# ReactionWheelPCB.net
KiCad netlist of a schematic drawn in Altium Designer
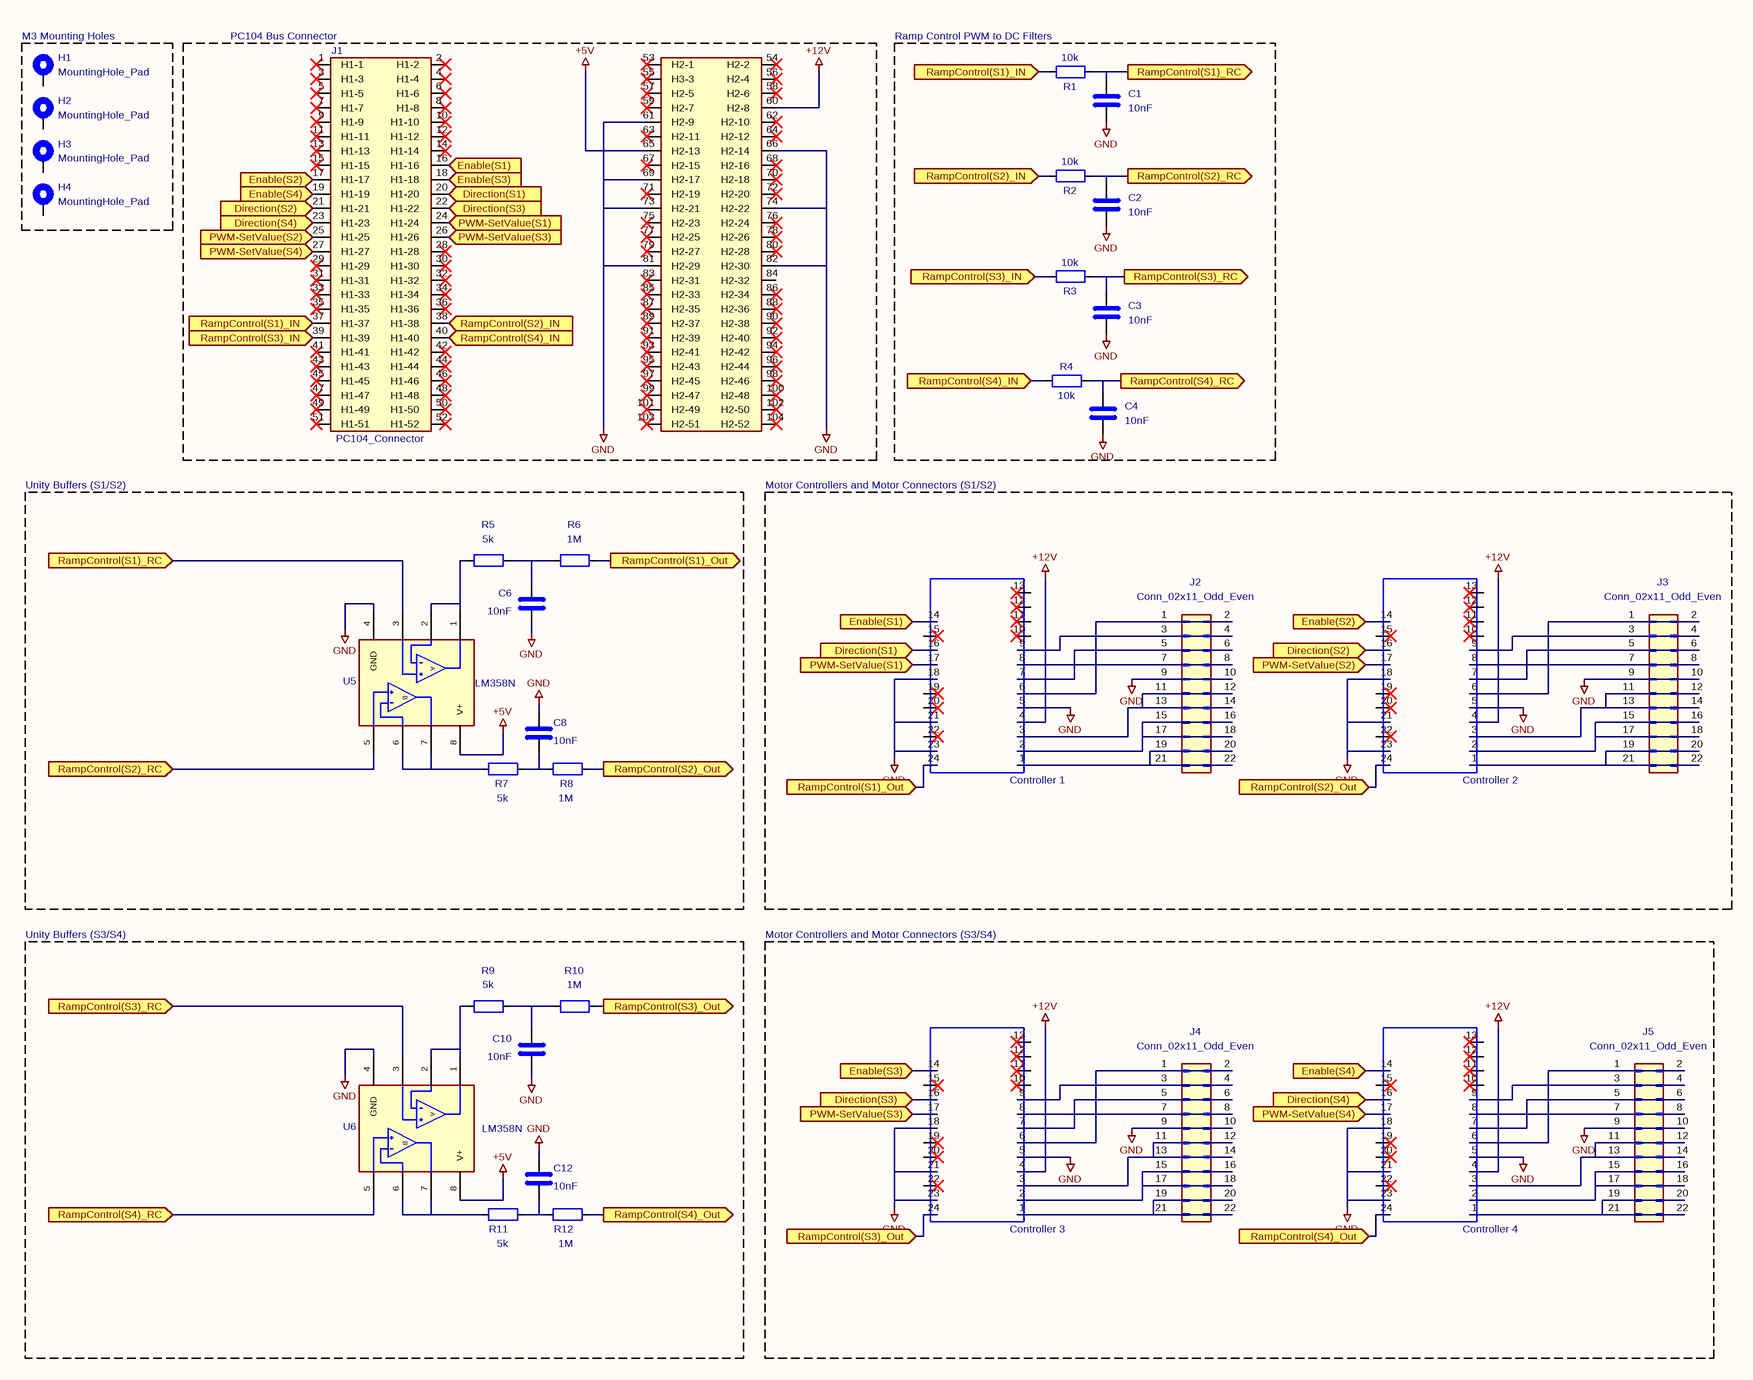
[diagram p0: ReactionWheelPCB.SchDoc]

(export (version "E")
  (design (tool "Eeschema 10.0.6"))
  (components
    (comp (ref "C1") (value "10nF") (libsource (lib "Device") (part "C")))
    (comp (ref "C2") (value "10nF") (libsource (lib "Device") (part "C")))
    (comp (ref "C3") (value "10nF") (libsource (lib "Device") (part "C")))
    (comp (ref "C4") (value "10nF") (libsource (lib "Device") (part "C")))
    (comp (ref "C6") (value "10nF") (libsource (lib "Device") (part "C")))
    (comp (ref "C8") (value "10nF") (libsource (lib "Device") (part "C")))
    (comp (ref "C10") (value "10nF") (libsource (lib "Device") (part "C")))
    (comp (ref "C12") (value "10nF") (libsource (lib "Device") (part "C")))
    (comp (ref "H1") (value "MountingHole_Pad") (libsource (lib "Mechanical") (part "MountingHole_Pad")))
    (comp (ref "H2") (value "MountingHole_Pad") (libsource (lib "Mechanical") (part "MountingHole_Pad")))
    (comp (ref "H3") (value "MountingHole_Pad") (libsource (lib "Mechanical") (part "MountingHole_Pad")))
    (comp (ref "H4") (value "MountingHole_Pad") (libsource (lib "Mechanical") (part "MountingHole_Pad")))
    (comp (ref "J1")
      (value "PC104_Connector")
      (libsource (lib "qset-connector-library") (part "PC104_Connector"))
    )
    (comp (ref "J2")
      (value "Conn_02x11_Odd_Even")
      (libsource (lib "Connector_Generic") (part "Conn_02x11_Odd_Even"))
    )
    (comp (ref "J3")
      (value "Conn_02x11_Odd_Even")
      (libsource (lib "Connector_Generic") (part "Conn_02x11_Odd_Even"))
    )
    (comp (ref "J4")
      (value "Conn_02x11_Odd_Even")
      (libsource (lib "Connector_Generic") (part "Conn_02x11_Odd_Even"))
    )
    (comp (ref "J5")
      (value "Conn_02x11_Odd_Even")
      (libsource (lib "Connector_Generic") (part "Conn_02x11_Odd_Even"))
    )
    (comp (ref "R1") (value "10k") (libsource (lib "") (part "R_1")))
    (comp (ref "R2") (value "10k") (libsource (lib "") (part "R_1")))
    (comp (ref "R3") (value "10k") (libsource (lib "") (part "R_1")))
    (comp (ref "R4") (value "10k") (libsource (lib "") (part "R_1")))
    (comp (ref "R5") (value "5k") (libsource (lib "Device") (part "R")))
    (comp (ref "R6") (value "1M") (libsource (lib "Device") (part "R")))
    (comp (ref "R7") (value "5k") (libsource (lib "") (part "R_1")))
    (comp (ref "R8") (value "1M") (libsource (lib "") (part "R_1")))
    (comp (ref "R9") (value "5k") (libsource (lib "Device") (part "R")))
    (comp (ref "R10") (value "1M") (libsource (lib "Device") (part "R")))
    (comp (ref "R11") (value "5k") (libsource (lib "") (part "R_1")))
    (comp (ref "R12") (value "1M") (libsource (lib "") (part "R_1")))
    (comp (ref "U1")
      (value "Controller 1")
      (libsource (lib "UpdatedControllerBoardSchematic-rescue") (part "Escon24.2-symbols-Controller_Board-rescue-UpdatedController-rescue"))
    )
    (comp (ref "U2")
      (value "Controller 2")
      (libsource (lib "UpdatedControllerBoardSchematic-rescue") (part "Escon24.2-symbols-Controller_Board-rescue-UpdatedController-rescue"))
    )
    (comp (ref "U3")
      (value "Controller 3")
      (libsource (lib "UpdatedControllerBoardSchematic-rescue") (part "Escon24.2-symbols-Controller_Board-rescue-UpdatedController-rescue"))
    )
    (comp (ref "U4")
      (value "Controller 4")
      (libsource (lib "UpdatedControllerBoardSchematic-rescue") (part "Escon24.2-symbols-Controller_Board-rescue-UpdatedController-rescue"))
    )
    (comp (ref "U5") (value "LM358N") (libsource (lib "ADCS_Symbols") (part "LM358")))
    (comp (ref "U6") (value "LM358N") (libsource (lib "ADCS_Symbols") (part "LM358")))
  )
  (nets
    (net (code "1") (name "+5V") (class "Default")
      (node (ref "J1") (pin "65") (pinfunction "H2-13_65") (pintype "passive"))
      (node (ref "U5") (pin "8") (pinfunction "V+_8") (pintype "passive"))
      (node (ref "U6") (pin "8") (pinfunction "V+_8") (pintype "passive"))
    )
    (net (code "2") (name "+12V") (class "Default")
      (node (ref "J1") (pin "60") (pinfunction "H2-8_60") (pintype "passive"))
      (node (ref "U1") (pin "4") (pinfunction "4_4") (pintype "passive"))
      (node (ref "U2") (pin "4") (pinfunction "4_4") (pintype "passive"))
      (node (ref "U3") (pin "4") (pinfunction "4_4") (pintype "passive"))
      (node (ref "U4") (pin "4") (pinfunction "4_4") (pintype "passive"))
    )
    (net (code "3") (name "/Direction(S1)") (class "Default")
      (node (ref "J1") (pin "20") (pinfunction "H1-20_20") (pintype "passive"))
      (node (ref "U1") (pin "16") (pinfunction "16_16") (pintype "passive"))
    )
    (net (code "4") (name "/Direction(S2)") (class "Default")
      (node (ref "J1") (pin "21") (pinfunction "H1-21_21") (pintype "passive"))
      (node (ref "U2") (pin "16") (pinfunction "16_16") (pintype "passive"))
    )
    (net (code "5") (name "/Direction(S3)") (class "Default")
      (node (ref "J1") (pin "22") (pinfunction "H1-22_22") (pintype "passive"))
      (node (ref "U3") (pin "16") (pinfunction "16_16") (pintype "passive"))
    )
    (net (code "6") (name "/Direction(S4)") (class "Default")
      (node (ref "J1") (pin "23") (pinfunction "H1-23_23") (pintype "passive"))
      (node (ref "U4") (pin "16") (pinfunction "16_16") (pintype "passive"))
    )
    (net (code "7") (name "/Enable(S1)") (class "Default")
      (node (ref "J1") (pin "16") (pinfunction "H1-16_16") (pintype "passive"))
      (node (ref "U1") (pin "14") (pinfunction "14_14") (pintype "passive"))
    )
    (net (code "8") (name "/Enable(S2)") (class "Default")
      (node (ref "J1") (pin "17") (pinfunction "H1-17_17") (pintype "passive"))
      (node (ref "U2") (pin "14") (pinfunction "14_14") (pintype "passive"))
    )
    (net (code "9") (name "/Enable(S3)") (class "Default")
      (node (ref "J1") (pin "18") (pinfunction "H1-18_18") (pintype "passive"))
      (node (ref "U3") (pin "14") (pinfunction "14_14") (pintype "passive"))
    )
    (net (code "10") (name "/Enable(S4)") (class "Default")
      (node (ref "J1") (pin "19") (pinfunction "H1-19_19") (pintype "passive"))
      (node (ref "U4") (pin "14") (pinfunction "14_14") (pintype "passive"))
    )
    (net (code "11") (name "/PWM-SetValue(S1)") (class "Default")
      (node (ref "J1") (pin "24") (pinfunction "H1-24_24") (pintype "passive"))
      (node (ref "U1") (pin "17") (pinfunction "17_17") (pintype "passive"))
    )
    (net (code "12") (name "/PWM-SetValue(S2)") (class "Default")
      (node (ref "J1") (pin "25") (pinfunction "H1-25_25") (pintype "passive"))
      (node (ref "U2") (pin "17") (pinfunction "17_17") (pintype "passive"))
    )
    (net (code "13") (name "/PWM-SetValue(S3)") (class "Default")
      (node (ref "J1") (pin "26") (pinfunction "H1-26_26") (pintype "passive"))
      (node (ref "U3") (pin "17") (pinfunction "17_17") (pintype "passive"))
    )
    (net (code "14") (name "/PWM-SetValue(S4)") (class "Default")
      (node (ref "J1") (pin "27") (pinfunction "H1-27_27") (pintype "passive"))
      (node (ref "U4") (pin "17") (pinfunction "17_17") (pintype "passive"))
    )
    (net (code "15") (name "/RampControl(S1)_IN") (class "Default")
      (node (ref "J1") (pin "37") (pinfunction "H1-37_37") (pintype "passive"))
      (node (ref "R1") (pin "1") (pinfunction "1_1") (pintype "passive"))
    )
    (net (code "16") (name "/RampControl(S1)_Out") (class "Default")
      (node (ref "R6") (pin "1") (pinfunction "1_1") (pintype "passive"))
      (node (ref "U1") (pin "24") (pinfunction "24_24") (pintype "passive"))
    )
    (net (code "17") (name "/RampControl(S1)_RC") (class "Default")
      (node (ref "C1") (pin "2") (pinfunction "2_2") (pintype "passive"))
      (node (ref "R1") (pin "2") (pinfunction "2_2") (pintype "passive"))
      (node (ref "U5") (pin "3") (pinfunction "3_3") (pintype "passive"))
    )
    (net (code "18") (name "/RampControl(S2)_IN") (class "Default")
      (node (ref "J1") (pin "38") (pinfunction "H1-38_38") (pintype "passive"))
      (node (ref "R2") (pin "1") (pinfunction "1_1") (pintype "passive"))
    )
    (net (code "19") (name "/RampControl(S2)_Out") (class "Default")
      (node (ref "R8") (pin "2") (pinfunction "2_2") (pintype "passive"))
      (node (ref "U2") (pin "24") (pinfunction "24_24") (pintype "passive"))
    )
    (net (code "20") (name "/RampControl(S2)_RC") (class "Default")
      (node (ref "C2") (pin "2") (pinfunction "2_2") (pintype "passive"))
      (node (ref "R2") (pin "2") (pinfunction "2_2") (pintype "passive"))
      (node (ref "U5") (pin "5") (pinfunction "5_5") (pintype "passive"))
    )
    (net (code "21") (name "/RampControl(S3)_IN") (class "Default")
      (node (ref "J1") (pin "39") (pinfunction "H1-39_39") (pintype "passive"))
      (node (ref "R3") (pin "1") (pinfunction "1_1") (pintype "passive"))
    )
    (net (code "22") (name "/RampControl(S3)_Out") (class "Default")
      (node (ref "R10") (pin "1") (pinfunction "1_1") (pintype "passive"))
      (node (ref "U3") (pin "24") (pinfunction "24_24") (pintype "passive"))
    )
    (net (code "23") (name "/RampControl(S3)_RC") (class "Default")
      (node (ref "C3") (pin "2") (pinfunction "2_2") (pintype "passive"))
      (node (ref "R3") (pin "2") (pinfunction "2_2") (pintype "passive"))
      (node (ref "U6") (pin "3") (pinfunction "3_3") (pintype "passive"))
    )
    (net (code "24") (name "/RampControl(S4)_IN") (class "Default")
      (node (ref "J1") (pin "40") (pinfunction "H1-40_40") (pintype "passive"))
      (node (ref "R4") (pin "1") (pinfunction "1_1") (pintype "passive"))
    )
    (net (code "25") (name "/RampControl(S4)_Out") (class "Default")
      (node (ref "R12") (pin "2") (pinfunction "2_2") (pintype "passive"))
      (node (ref "U4") (pin "24") (pinfunction "24_24") (pintype "passive"))
    )
    (net (code "26") (name "/RampControl(S4)_RC") (class "Default")
      (node (ref "C4") (pin "2") (pinfunction "2_2") (pintype "passive"))
      (node (ref "R4") (pin "2") (pinfunction "2_2") (pintype "passive"))
      (node (ref "U6") (pin "5") (pinfunction "5_5") (pintype "passive"))
    )
    (net (code "27") (name "GND") (class "Default")
      (node (ref "C1") (pin "1") (pinfunction "1_1") (pintype "passive"))
      (node (ref "C10") (pin "1") (pinfunction "1_1") (pintype "passive"))
      (node (ref "C12") (pin "1") (pinfunction "1_1") (pintype "passive"))
      (node (ref "C2") (pin "1") (pinfunction "1_1") (pintype "passive"))
      (node (ref "C3") (pin "1") (pinfunction "1_1") (pintype "passive"))
      (node (ref "C4") (pin "1") (pinfunction "1_1") (pintype "passive"))
      (node (ref "C6") (pin "1") (pinfunction "1_1") (pintype "passive"))
      (node (ref "C8") (pin "1") (pinfunction "1_1") (pintype "passive"))
      (node (ref "J1") (pin "61") (pinfunction "H2-9_61") (pintype "passive"))
      (node (ref "J1") (pin "66") (pinfunction "H2-14_66") (pintype "passive"))
      (node (ref "J1") (pin "69") (pinfunction "H2-17_69") (pintype "passive"))
      (node (ref "J1") (pin "73") (pinfunction "H2-21_73") (pintype "passive"))
      (node (ref "J1") (pin "74") (pinfunction "H2-22_74") (pintype "passive"))
      (node (ref "J1") (pin "81") (pinfunction "H2-29_81") (pintype "passive"))
      (node (ref "J1") (pin "82") (pinfunction "H2-30_82") (pintype "passive"))
      (node (ref "J2") (pin "10") (pinfunction "Pin_10_10") (pintype "passive"))
      (node (ref "J2") (pin "9") (pinfunction "Pin_9_9") (pintype "passive"))
      (node (ref "J3") (pin "10") (pinfunction "Pin_10_10") (pintype "passive"))
      (node (ref "J3") (pin "9") (pinfunction "Pin_9_9") (pintype "passive"))
      (node (ref "J4") (pin "10") (pinfunction "Pin_10_10") (pintype "passive"))
      (node (ref "J4") (pin "9") (pinfunction "Pin_9_9") (pintype "passive"))
      (node (ref "J5") (pin "10") (pinfunction "Pin_10_10") (pintype "passive"))
      (node (ref "J5") (pin "9") (pinfunction "Pin_9_9") (pintype "passive"))
      (node (ref "U1") (pin "18") (pinfunction "18_18") (pintype "passive"))
      (node (ref "U1") (pin "21") (pinfunction "21_21") (pintype "passive"))
      (node (ref "U1") (pin "23") (pinfunction "23_23") (pintype "passive"))
      (node (ref "U1") (pin "5") (pinfunction "5_5") (pintype "passive"))
      (node (ref "U2") (pin "18") (pinfunction "18_18") (pintype "passive"))
      (node (ref "U2") (pin "21") (pinfunction "21_21") (pintype "passive"))
      (node (ref "U2") (pin "23") (pinfunction "23_23") (pintype "passive"))
      (node (ref "U2") (pin "5") (pinfunction "5_5") (pintype "passive"))
      (node (ref "U3") (pin "18") (pinfunction "18_18") (pintype "passive"))
      (node (ref "U3") (pin "21") (pinfunction "21_21") (pintype "passive"))
      (node (ref "U3") (pin "23") (pinfunction "23_23") (pintype "passive"))
      (node (ref "U3") (pin "5") (pinfunction "5_5") (pintype "passive"))
      (node (ref "U4") (pin "18") (pinfunction "18_18") (pintype "passive"))
      (node (ref "U4") (pin "21") (pinfunction "21_21") (pintype "passive"))
      (node (ref "U4") (pin "23") (pinfunction "23_23") (pintype "passive"))
      (node (ref "U4") (pin "5") (pinfunction "5_5") (pintype "passive"))
      (node (ref "U5") (pin "4") (pinfunction "GND_4") (pintype "passive"))
      (node (ref "U6") (pin "4") (pinfunction "GND_4") (pintype "passive"))
    )
    (net (code "28") (name "Net-(C6-Pad2)") (class "Default")
      (node (ref "C6") (pin "2") (pinfunction "2_2") (pintype "passive"))
      (node (ref "R5") (pin "1") (pinfunction "1_1") (pintype "passive"))
      (node (ref "R6") (pin "2") (pinfunction "2_2") (pintype "passive"))
    )
    (net (code "29") (name "Net-(C8-Pad2)") (class "Default")
      (node (ref "C8") (pin "2") (pinfunction "2_2") (pintype "passive"))
      (node (ref "R7") (pin "2") (pinfunction "2_2") (pintype "passive"))
      (node (ref "R8") (pin "1") (pinfunction "1_1") (pintype "passive"))
    )
    (net (code "30") (name "Net-(C10-Pad2)") (class "Default")
      (node (ref "C10") (pin "2") (pinfunction "2_2") (pintype "passive"))
      (node (ref "R10") (pin "2") (pinfunction "2_2") (pintype "passive"))
      (node (ref "R9") (pin "1") (pinfunction "1_1") (pintype "passive"))
    )
    (net (code "31") (name "Net-(C12-Pad2)") (class "Default")
      (node (ref "C12") (pin "2") (pinfunction "2_2") (pintype "passive"))
      (node (ref "R11") (pin "2") (pinfunction "2_2") (pintype "passive"))
      (node (ref "R12") (pin "1") (pinfunction "1_1") (pintype "passive"))
    )
    (net (code "32") (name "Net-(J2-Pin_1)") (class "Default")
      (node (ref "J2") (pin "1") (pinfunction "Pin_1_1") (pintype "passive"))
      (node (ref "J2") (pin "2") (pinfunction "Pin_2_2") (pintype "passive"))
      (node (ref "U1") (pin "6") (pinfunction "6_6") (pintype "passive"))
    )
    (net (code "33") (name "Net-(J2-Pin_3)") (class "Default")
      (node (ref "J2") (pin "3") (pinfunction "Pin_3_3") (pintype "passive"))
      (node (ref "J2") (pin "4") (pinfunction "Pin_4_4") (pintype "passive"))
      (node (ref "U1") (pin "9") (pinfunction "9_9") (pintype "passive"))
    )
    (net (code "34") (name "Net-(J2-Pin_5)") (class "Default")
      (node (ref "J2") (pin "5") (pinfunction "Pin_5_5") (pintype "passive"))
      (node (ref "J2") (pin "6") (pinfunction "Pin_6_6") (pintype "passive"))
      (node (ref "U1") (pin "7") (pinfunction "7_7") (pintype "passive"))
    )
    (net (code "35") (name "Net-(J2-Pin_7)") (class "Default")
      (node (ref "J2") (pin "7") (pinfunction "Pin_7_7") (pintype "passive"))
      (node (ref "J2") (pin "8") (pinfunction "Pin_8_8") (pintype "passive"))
      (node (ref "U1") (pin "8") (pinfunction "8_8") (pintype "passive"))
    )
    (net (code "36") (name "Net-(J2-Pin_11)") (class "Default")
      (node (ref "J2") (pin "11") (pinfunction "Pin_11_11") (pintype "passive"))
      (node (ref "J2") (pin "12") (pinfunction "Pin_12_12") (pintype "passive"))
      (node (ref "J2") (pin "13") (pinfunction "Pin_13_13") (pintype "passive"))
      (node (ref "J2") (pin "14") (pinfunction "Pin_14_14") (pintype "passive"))
      (node (ref "U1") (pin "3") (pinfunction "3_3") (pintype "passive"))
    )
    (net (code "37") (name "Net-(J2-Pin_15)") (class "Default")
      (node (ref "J2") (pin "15") (pinfunction "Pin_15_15") (pintype "passive"))
      (node (ref "J2") (pin "16") (pinfunction "Pin_16_16") (pintype "passive"))
      (node (ref "J2") (pin "17") (pinfunction "Pin_17_17") (pintype "passive"))
      (node (ref "J2") (pin "18") (pinfunction "Pin_18_18") (pintype "passive"))
      (node (ref "U1") (pin "2") (pinfunction "2_2") (pintype "passive"))
    )
    (net (code "38") (name "Net-(J2-Pin_19)") (class "Default")
      (node (ref "J2") (pin "19") (pinfunction "Pin_19_19") (pintype "passive"))
      (node (ref "J2") (pin "20") (pinfunction "Pin_20_20") (pintype "passive"))
      (node (ref "J2") (pin "21") (pinfunction "Pin_21_21") (pintype "passive"))
      (node (ref "J2") (pin "22") (pinfunction "Pin_22_22") (pintype "passive"))
      (node (ref "U1") (pin "1") (pinfunction "1_1") (pintype "passive"))
    )
    (net (code "39") (name "Net-(J3-Pin_1)") (class "Default")
      (node (ref "J3") (pin "1") (pinfunction "Pin_1_1") (pintype "passive"))
      (node (ref "J3") (pin "2") (pinfunction "Pin_2_2") (pintype "passive"))
      (node (ref "U2") (pin "6") (pinfunction "6_6") (pintype "passive"))
    )
    (net (code "40") (name "Net-(J3-Pin_3)") (class "Default")
      (node (ref "J3") (pin "3") (pinfunction "Pin_3_3") (pintype "passive"))
      (node (ref "J3") (pin "4") (pinfunction "Pin_4_4") (pintype "passive"))
      (node (ref "U2") (pin "9") (pinfunction "9_9") (pintype "passive"))
    )
    (net (code "41") (name "Net-(J3-Pin_5)") (class "Default")
      (node (ref "J3") (pin "5") (pinfunction "Pin_5_5") (pintype "passive"))
      (node (ref "J3") (pin "6") (pinfunction "Pin_6_6") (pintype "passive"))
      (node (ref "U2") (pin "7") (pinfunction "7_7") (pintype "passive"))
    )
    (net (code "42") (name "Net-(J3-Pin_7)") (class "Default")
      (node (ref "J3") (pin "7") (pinfunction "Pin_7_7") (pintype "passive"))
      (node (ref "J3") (pin "8") (pinfunction "Pin_8_8") (pintype "passive"))
      (node (ref "U2") (pin "8") (pinfunction "8_8") (pintype "passive"))
    )
    (net (code "43") (name "Net-(J3-Pin_11)") (class "Default")
      (node (ref "J3") (pin "11") (pinfunction "Pin_11_11") (pintype "passive"))
      (node (ref "J3") (pin "12") (pinfunction "Pin_12_12") (pintype "passive"))
      (node (ref "J3") (pin "13") (pinfunction "Pin_13_13") (pintype "passive"))
      (node (ref "J3") (pin "14") (pinfunction "Pin_14_14") (pintype "passive"))
      (node (ref "U2") (pin "3") (pinfunction "3_3") (pintype "passive"))
    )
    (net (code "44") (name "Net-(J3-Pin_15)") (class "Default")
      (node (ref "J3") (pin "15") (pinfunction "Pin_15_15") (pintype "passive"))
      (node (ref "J3") (pin "16") (pinfunction "Pin_16_16") (pintype "passive"))
      (node (ref "J3") (pin "17") (pinfunction "Pin_17_17") (pintype "passive"))
      (node (ref "J3") (pin "18") (pinfunction "Pin_18_18") (pintype "passive"))
      (node (ref "U2") (pin "2") (pinfunction "2_2") (pintype "passive"))
    )
    (net (code "45") (name "Net-(J3-Pin_19)") (class "Default")
      (node (ref "J3") (pin "19") (pinfunction "Pin_19_19") (pintype "passive"))
      (node (ref "J3") (pin "20") (pinfunction "Pin_20_20") (pintype "passive"))
      (node (ref "J3") (pin "21") (pinfunction "Pin_21_21") (pintype "passive"))
      (node (ref "J3") (pin "22") (pinfunction "Pin_22_22") (pintype "passive"))
      (node (ref "U2") (pin "1") (pinfunction "1_1") (pintype "passive"))
    )
    (net (code "46") (name "Net-(J4-Pin_1)") (class "Default")
      (node (ref "J4") (pin "1") (pinfunction "Pin_1_1") (pintype "passive"))
      (node (ref "J4") (pin "2") (pinfunction "Pin_2_2") (pintype "passive"))
      (node (ref "U3") (pin "6") (pinfunction "6_6") (pintype "passive"))
    )
    (net (code "47") (name "Net-(J4-Pin_3)") (class "Default")
      (node (ref "J4") (pin "3") (pinfunction "Pin_3_3") (pintype "passive"))
      (node (ref "J4") (pin "4") (pinfunction "Pin_4_4") (pintype "passive"))
      (node (ref "U3") (pin "9") (pinfunction "9_9") (pintype "passive"))
    )
    (net (code "48") (name "Net-(J4-Pin_5)") (class "Default")
      (node (ref "J4") (pin "5") (pinfunction "Pin_5_5") (pintype "passive"))
      (node (ref "J4") (pin "6") (pinfunction "Pin_6_6") (pintype "passive"))
      (node (ref "U3") (pin "7") (pinfunction "7_7") (pintype "passive"))
    )
    (net (code "49") (name "Net-(J4-Pin_7)") (class "Default")
      (node (ref "J4") (pin "7") (pinfunction "Pin_7_7") (pintype "passive"))
      (node (ref "J4") (pin "8") (pinfunction "Pin_8_8") (pintype "passive"))
      (node (ref "U3") (pin "8") (pinfunction "8_8") (pintype "passive"))
    )
    (net (code "50") (name "Net-(J4-Pin_11)") (class "Default")
      (node (ref "J4") (pin "11") (pinfunction "Pin_11_11") (pintype "passive"))
      (node (ref "J4") (pin "12") (pinfunction "Pin_12_12") (pintype "passive"))
      (node (ref "J4") (pin "13") (pinfunction "Pin_13_13") (pintype "passive"))
      (node (ref "J4") (pin "14") (pinfunction "Pin_14_14") (pintype "passive"))
      (node (ref "U3") (pin "3") (pinfunction "3_3") (pintype "passive"))
    )
    (net (code "51") (name "Net-(J4-Pin_15)") (class "Default")
      (node (ref "J4") (pin "15") (pinfunction "Pin_15_15") (pintype "passive"))
      (node (ref "J4") (pin "16") (pinfunction "Pin_16_16") (pintype "passive"))
      (node (ref "J4") (pin "17") (pinfunction "Pin_17_17") (pintype "passive"))
      (node (ref "J4") (pin "18") (pinfunction "Pin_18_18") (pintype "passive"))
      (node (ref "U3") (pin "2") (pinfunction "2_2") (pintype "passive"))
    )
    (net (code "52") (name "Net-(J4-Pin_19)") (class "Default")
      (node (ref "J4") (pin "19") (pinfunction "Pin_19_19") (pintype "passive"))
      (node (ref "J4") (pin "20") (pinfunction "Pin_20_20") (pintype "passive"))
      (node (ref "J4") (pin "21") (pinfunction "Pin_21_21") (pintype "passive"))
      (node (ref "J4") (pin "22") (pinfunction "Pin_22_22") (pintype "passive"))
      (node (ref "U3") (pin "1") (pinfunction "1_1") (pintype "passive"))
    )
    (net (code "53") (name "Net-(J5-Pin_1)") (class "Default")
      (node (ref "J5") (pin "1") (pinfunction "Pin_1_1") (pintype "passive"))
      (node (ref "J5") (pin "2") (pinfunction "Pin_2_2") (pintype "passive"))
      (node (ref "U4") (pin "6") (pinfunction "6_6") (pintype "passive"))
    )
    (net (code "54") (name "Net-(J5-Pin_3)") (class "Default")
      (node (ref "J5") (pin "3") (pinfunction "Pin_3_3") (pintype "passive"))
      (node (ref "J5") (pin "4") (pinfunction "Pin_4_4") (pintype "passive"))
      (node (ref "U4") (pin "9") (pinfunction "9_9") (pintype "passive"))
    )
    (net (code "55") (name "Net-(J5-Pin_5)") (class "Default")
      (node (ref "J5") (pin "5") (pinfunction "Pin_5_5") (pintype "passive"))
      (node (ref "J5") (pin "6") (pinfunction "Pin_6_6") (pintype "passive"))
      (node (ref "U4") (pin "7") (pinfunction "7_7") (pintype "passive"))
    )
    (net (code "56") (name "Net-(J5-Pin_7)") (class "Default")
      (node (ref "J5") (pin "7") (pinfunction "Pin_7_7") (pintype "passive"))
      (node (ref "J5") (pin "8") (pinfunction "Pin_8_8") (pintype "passive"))
      (node (ref "U4") (pin "8") (pinfunction "8_8") (pintype "passive"))
    )
    (net (code "57") (name "Net-(J5-Pin_11)") (class "Default")
      (node (ref "J5") (pin "11") (pinfunction "Pin_11_11") (pintype "passive"))
      (node (ref "J5") (pin "12") (pinfunction "Pin_12_12") (pintype "passive"))
      (node (ref "J5") (pin "13") (pinfunction "Pin_13_13") (pintype "passive"))
      (node (ref "J5") (pin "14") (pinfunction "Pin_14_14") (pintype "passive"))
      (node (ref "U4") (pin "3") (pinfunction "3_3") (pintype "passive"))
    )
    (net (code "58") (name "Net-(J5-Pin_15)") (class "Default")
      (node (ref "J5") (pin "15") (pinfunction "Pin_15_15") (pintype "passive"))
      (node (ref "J5") (pin "16") (pinfunction "Pin_16_16") (pintype "passive"))
      (node (ref "J5") (pin "17") (pinfunction "Pin_17_17") (pintype "passive"))
      (node (ref "J5") (pin "18") (pinfunction "Pin_18_18") (pintype "passive"))
      (node (ref "U4") (pin "2") (pinfunction "2_2") (pintype "passive"))
    )
    (net (code "59") (name "Net-(J5-Pin_19)") (class "Default")
      (node (ref "J5") (pin "19") (pinfunction "Pin_19_19") (pintype "passive"))
      (node (ref "J5") (pin "20") (pinfunction "Pin_20_20") (pintype "passive"))
      (node (ref "J5") (pin "21") (pinfunction "Pin_21_21") (pintype "passive"))
      (node (ref "J5") (pin "22") (pinfunction "Pin_22_22") (pintype "passive"))
      (node (ref "U4") (pin "1") (pinfunction "1_1") (pintype "passive"))
    )
    (net (code "60") (name "Net-(R5-Pad2)") (class "Default")
      (node (ref "R5") (pin "2") (pinfunction "2_2") (pintype "passive"))
      (node (ref "U5") (pin "1") (pinfunction "1_1") (pintype "passive"))
      (node (ref "U5") (pin "2") (pinfunction "2_2") (pintype "passive"))
    )
    (net (code "61") (name "Net-(R7-Pad1)") (class "Default")
      (node (ref "R7") (pin "1") (pinfunction "1_1") (pintype "passive"))
      (node (ref "U5") (pin "6") (pinfunction "6_6") (pintype "passive"))
      (node (ref "U5") (pin "7") (pinfunction "7_7") (pintype "passive"))
    )
    (net (code "62") (name "Net-(R9-Pad2)") (class "Default")
      (node (ref "R9") (pin "2") (pinfunction "2_2") (pintype "passive"))
      (node (ref "U6") (pin "1") (pinfunction "1_1") (pintype "passive"))
      (node (ref "U6") (pin "2") (pinfunction "2_2") (pintype "passive"))
    )
    (net (code "63") (name "Net-(R11-Pad1)") (class "Default")
      (node (ref "R11") (pin "1") (pinfunction "1_1") (pintype "passive"))
      (node (ref "U6") (pin "6") (pinfunction "6_6") (pintype "passive"))
      (node (ref "U6") (pin "7") (pinfunction "7_7") (pintype "passive"))
    )
    (net (code "64") (name "unconnected-(H1-Pad1)") (class "Default")
      (node (ref "H1") (pin "1") (pinfunction "1_1") (pintype "passive"))
    )
    (net (code "65") (name "unconnected-(H2-Pad1)") (class "Default")
      (node (ref "H2") (pin "1") (pinfunction "1_1") (pintype "passive"))
    )
    (net (code "66") (name "unconnected-(H3-Pad1)") (class "Default")
      (node (ref "H3") (pin "1") (pinfunction "1_1") (pintype "passive"))
    )
    (net (code "67") (name "unconnected-(H4-Pad1)") (class "Default")
      (node (ref "H4") (pin "1") (pinfunction "1_1") (pintype "passive"))
    )
    (net (code "68") (name "unconnected-(J1-H1-1-Pad1)") (class "Default")
      (node (ref "J1") (pin "1") (pinfunction "H1-1_1") (pintype "passive+no_connect"))
    )
    (net (code "69") (name "unconnected-(J1-H1-2-Pad2)") (class "Default")
      (node (ref "J1") (pin "2") (pinfunction "H1-2_2") (pintype "passive+no_connect"))
    )
    (net (code "70") (name "unconnected-(J1-H1-3-Pad3)") (class "Default")
      (node (ref "J1") (pin "3") (pinfunction "H1-3_3") (pintype "passive+no_connect"))
    )
    (net (code "71") (name "unconnected-(J1-H1-4-Pad4)") (class "Default")
      (node (ref "J1") (pin "4") (pinfunction "H1-4_4") (pintype "passive+no_connect"))
    )
    (net (code "72") (name "unconnected-(J1-H1-5-Pad5)") (class "Default")
      (node (ref "J1") (pin "5") (pinfunction "H1-5_5") (pintype "passive+no_connect"))
    )
    (net (code "73") (name "unconnected-(J1-H1-6-Pad6)") (class "Default")
      (node (ref "J1") (pin "6") (pinfunction "H1-6_6") (pintype "passive+no_connect"))
    )
    (net (code "74") (name "unconnected-(J1-H1-7-Pad7)") (class "Default")
      (node (ref "J1") (pin "7") (pinfunction "H1-7_7") (pintype "passive+no_connect"))
    )
    (net (code "75") (name "unconnected-(J1-H1-8-Pad8)") (class "Default")
      (node (ref "J1") (pin "8") (pinfunction "H1-8_8") (pintype "passive+no_connect"))
    )
    (net (code "76") (name "unconnected-(J1-H1-9-Pad9)") (class "Default")
      (node (ref "J1") (pin "9") (pinfunction "H1-9_9") (pintype "passive+no_connect"))
    )
    (net (code "77") (name "unconnected-(J1-H1-10-Pad10)") (class "Default")
      (node (ref "J1") (pin "10") (pinfunction "H1-10_10") (pintype "passive+no_connect"))
    )
    (net (code "78") (name "unconnected-(J1-H1-11-Pad11)") (class "Default")
      (node (ref "J1") (pin "11") (pinfunction "H1-11_11") (pintype "passive+no_connect"))
    )
    (net (code "79") (name "unconnected-(J1-H1-12-Pad12)") (class "Default")
      (node (ref "J1") (pin "12") (pinfunction "H1-12_12") (pintype "passive+no_connect"))
    )
    (net (code "80") (name "unconnected-(J1-H1-13-Pad13)") (class "Default")
      (node (ref "J1") (pin "13") (pinfunction "H1-13_13") (pintype "passive+no_connect"))
    )
    (net (code "81") (name "unconnected-(J1-H1-14-Pad14)") (class "Default")
      (node (ref "J1") (pin "14") (pinfunction "H1-14_14") (pintype "passive+no_connect"))
    )
    (net (code "82") (name "unconnected-(J1-H1-15-Pad15)") (class "Default")
      (node (ref "J1") (pin "15") (pinfunction "H1-15_15") (pintype "passive+no_connect"))
    )
    (net (code "83") (name "unconnected-(J1-H1-28-Pad28)") (class "Default")
      (node (ref "J1") (pin "28") (pinfunction "H1-28_28") (pintype "passive+no_connect"))
    )
    (net (code "84") (name "unconnected-(J1-H1-29-Pad29)") (class "Default")
      (node (ref "J1") (pin "29") (pinfunction "H1-29_29") (pintype "passive+no_connect"))
    )
    (net (code "85") (name "unconnected-(J1-H1-30-Pad30)") (class "Default")
      (node (ref "J1") (pin "30") (pinfunction "H1-30_30") (pintype "passive+no_connect"))
    )
    (net (code "86") (name "unconnected-(J1-H1-31-Pad31)") (class "Default")
      (node (ref "J1") (pin "31") (pinfunction "H1-31_31") (pintype "passive+no_connect"))
    )
    (net (code "87") (name "unconnected-(J1-H1-32-Pad32)") (class "Default")
      (node (ref "J1") (pin "32") (pinfunction "H1-32_32") (pintype "passive+no_connect"))
    )
    (net (code "88") (name "unconnected-(J1-H1-33-Pad33)") (class "Default")
      (node (ref "J1") (pin "33") (pinfunction "H1-33_33") (pintype "passive+no_connect"))
    )
    (net (code "89") (name "unconnected-(J1-H1-34-Pad34)") (class "Default")
      (node (ref "J1") (pin "34") (pinfunction "H1-34_34") (pintype "passive+no_connect"))
    )
    (net (code "90") (name "unconnected-(J1-H1-35-Pad35)") (class "Default")
      (node (ref "J1") (pin "35") (pinfunction "H1-35_35") (pintype "passive+no_connect"))
    )
    (net (code "91") (name "unconnected-(J1-H1-36-Pad36)") (class "Default")
      (node (ref "J1") (pin "36") (pinfunction "H1-36_36") (pintype "passive+no_connect"))
    )
    (net (code "92") (name "unconnected-(J1-H1-41-Pad41)") (class "Default")
      (node (ref "J1") (pin "41") (pinfunction "H1-41_41") (pintype "passive+no_connect"))
    )
    (net (code "93") (name "unconnected-(J1-H1-42-Pad42)") (class "Default")
      (node (ref "J1") (pin "42") (pinfunction "H1-42_42") (pintype "passive+no_connect"))
    )
    (net (code "94") (name "unconnected-(J1-H1-43-Pad43)") (class "Default")
      (node (ref "J1") (pin "43") (pinfunction "H1-43_43") (pintype "passive+no_connect"))
    )
    (net (code "95") (name "unconnected-(J1-H1-44-Pad44)") (class "Default")
      (node (ref "J1") (pin "44") (pinfunction "H1-44_44") (pintype "passive+no_connect"))
    )
    (net (code "96") (name "unconnected-(J1-H1-45-Pad45)") (class "Default")
      (node (ref "J1") (pin "45") (pinfunction "H1-45_45") (pintype "passive+no_connect"))
    )
    (net (code "97") (name "unconnected-(J1-H1-46-Pad46)") (class "Default")
      (node (ref "J1") (pin "46") (pinfunction "H1-46_46") (pintype "passive+no_connect"))
    )
    (net (code "98") (name "unconnected-(J1-H1-47-Pad47)") (class "Default")
      (node (ref "J1") (pin "47") (pinfunction "H1-47_47") (pintype "passive+no_connect"))
    )
    (net (code "99") (name "unconnected-(J1-H1-48-Pad48)") (class "Default")
      (node (ref "J1") (pin "48") (pinfunction "H1-48_48") (pintype "passive+no_connect"))
    )
    (net (code "100") (name "unconnected-(J1-H1-49-Pad49)") (class "Default")
      (node (ref "J1") (pin "49") (pinfunction "H1-49_49") (pintype "passive+no_connect"))
    )
    (net (code "101") (name "unconnected-(J1-H1-50-Pad50)") (class "Default")
      (node (ref "J1") (pin "50") (pinfunction "H1-50_50") (pintype "passive+no_connect"))
    )
    (net (code "102") (name "unconnected-(J1-H1-51-Pad51)") (class "Default")
      (node (ref "J1") (pin "51") (pinfunction "H1-51_51") (pintype "passive+no_connect"))
    )
    (net (code "103") (name "unconnected-(J1-H1-52-Pad52)") (class "Default")
      (node (ref "J1") (pin "52") (pinfunction "H1-52_52") (pintype "passive+no_connect"))
    )
    (net (code "104") (name "unconnected-(J1-H2-1-Pad53)") (class "Default")
      (node (ref "J1") (pin "53") (pinfunction "H2-1_53") (pintype "passive+no_connect"))
    )
    (net (code "105") (name "unconnected-(J1-H2-2-Pad54)") (class "Default")
      (node (ref "J1") (pin "54") (pinfunction "H2-2_54") (pintype "passive+no_connect"))
    )
    (net (code "106") (name "unconnected-(J1-H2-4-Pad56)") (class "Default")
      (node (ref "J1") (pin "56") (pinfunction "H2-4_56") (pintype "passive+no_connect"))
    )
    (net (code "107") (name "unconnected-(J1-H2-5-Pad57)") (class "Default")
      (node (ref "J1") (pin "57") (pinfunction "H2-5_57") (pintype "passive+no_connect"))
    )
    (net (code "108") (name "unconnected-(J1-H2-6-Pad58)") (class "Default")
      (node (ref "J1") (pin "58") (pinfunction "H2-6_58") (pintype "passive+no_connect"))
    )
    (net (code "109") (name "unconnected-(J1-H2-7-Pad59)") (class "Default")
      (node (ref "J1") (pin "59") (pinfunction "H2-7_59") (pintype "passive+no_connect"))
    )
    (net (code "110") (name "unconnected-(J1-H2-10-Pad62)") (class "Default")
      (node (ref "J1") (pin "62") (pinfunction "H2-10_62") (pintype "passive+no_connect"))
    )
    (net (code "111") (name "unconnected-(J1-H2-11-Pad63)") (class "Default")
      (node (ref "J1") (pin "63") (pinfunction "H2-11_63") (pintype "passive+no_connect"))
    )
    (net (code "112") (name "unconnected-(J1-H2-12-Pad64)") (class "Default")
      (node (ref "J1") (pin "64") (pinfunction "H2-12_64") (pintype "passive+no_connect"))
    )
    (net (code "113") (name "unconnected-(J1-H2-15-Pad67)") (class "Default")
      (node (ref "J1") (pin "67") (pinfunction "H2-15_67") (pintype "passive+no_connect"))
    )
    (net (code "114") (name "unconnected-(J1-H2-16-Pad68)") (class "Default")
      (node (ref "J1") (pin "68") (pinfunction "H2-16_68") (pintype "passive+no_connect"))
    )
    (net (code "115") (name "unconnected-(J1-H2-18-Pad70)") (class "Default")
      (node (ref "J1") (pin "70") (pinfunction "H2-18_70") (pintype "passive+no_connect"))
    )
    (net (code "116") (name "unconnected-(J1-H2-19-Pad71)") (class "Default")
      (node (ref "J1") (pin "71") (pinfunction "H2-19_71") (pintype "passive+no_connect"))
    )
    (net (code "117") (name "unconnected-(J1-H2-20-Pad72)") (class "Default")
      (node (ref "J1") (pin "72") (pinfunction "H2-20_72") (pintype "passive+no_connect"))
    )
    (net (code "118") (name "unconnected-(J1-H2-23-Pad75)") (class "Default")
      (node (ref "J1") (pin "75") (pinfunction "H2-23_75") (pintype "passive+no_connect"))
    )
    (net (code "119") (name "unconnected-(J1-H2-24-Pad76)") (class "Default")
      (node (ref "J1") (pin "76") (pinfunction "H2-24_76") (pintype "passive+no_connect"))
    )
    (net (code "120") (name "unconnected-(J1-H2-25-Pad77)") (class "Default")
      (node (ref "J1") (pin "77") (pinfunction "H2-25_77") (pintype "passive+no_connect"))
    )
    (net (code "121") (name "unconnected-(J1-H2-26-Pad78)") (class "Default")
      (node (ref "J1") (pin "78") (pinfunction "H2-26_78") (pintype "passive+no_connect"))
    )
    (net (code "122") (name "unconnected-(J1-H2-27-Pad79)") (class "Default")
      (node (ref "J1") (pin "79") (pinfunction "H2-27_79") (pintype "passive+no_connect"))
    )
    (net (code "123") (name "unconnected-(J1-H2-28-Pad80)") (class "Default")
      (node (ref "J1") (pin "80") (pinfunction "H2-28_80") (pintype "passive+no_connect"))
    )
    (net (code "124") (name "unconnected-(J1-H2-31-Pad83)") (class "Default")
      (node (ref "J1") (pin "83") (pinfunction "H2-31_83") (pintype "passive+no_connect"))
    )
    (net (code "125") (name "unconnected-(J1-H2-32-Pad84)") (class "Default")
      (node (ref "J1") (pin "84") (pinfunction "H2-32_84") (pintype "passive"))
    )
    (net (code "126") (name "unconnected-(J1-H2-33-Pad85)") (class "Default")
      (node (ref "J1") (pin "85") (pinfunction "H2-33_85") (pintype "passive+no_connect"))
    )
    (net (code "127") (name "unconnected-(J1-H2-34-Pad86)") (class "Default")
      (node (ref "J1") (pin "86") (pinfunction "H2-34_86") (pintype "passive+no_connect"))
    )
    (net (code "128") (name "unconnected-(J1-H2-35-Pad87)") (class "Default")
      (node (ref "J1") (pin "87") (pinfunction "H2-35_87") (pintype "passive+no_connect"))
    )
    (net (code "129") (name "unconnected-(J1-H2-36-Pad88)") (class "Default")
      (node (ref "J1") (pin "88") (pinfunction "H2-36_88") (pintype "passive+no_connect"))
    )
    (net (code "130") (name "unconnected-(J1-H2-37-Pad89)") (class "Default")
      (node (ref "J1") (pin "89") (pinfunction "H2-37_89") (pintype "passive+no_connect"))
    )
    (net (code "131") (name "unconnected-(J1-H2-38-Pad90)") (class "Default")
      (node (ref "J1") (pin "90") (pinfunction "H2-38_90") (pintype "passive+no_connect"))
    )
    (net (code "132") (name "unconnected-(J1-H2-39-Pad91)") (class "Default")
      (node (ref "J1") (pin "91") (pinfunction "H2-39_91") (pintype "passive+no_connect"))
    )
    (net (code "133") (name "unconnected-(J1-H2-40-Pad92)") (class "Default")
      (node (ref "J1") (pin "92") (pinfunction "H2-40_92") (pintype "passive+no_connect"))
    )
    (net (code "134") (name "unconnected-(J1-H2-41-Pad93)") (class "Default")
      (node (ref "J1") (pin "93") (pinfunction "H2-41_93") (pintype "passive+no_connect"))
    )
    (net (code "135") (name "unconnected-(J1-H2-42-Pad94)") (class "Default")
      (node (ref "J1") (pin "94") (pinfunction "H2-42_94") (pintype "passive+no_connect"))
    )
    (net (code "136") (name "unconnected-(J1-H2-43-Pad95)") (class "Default")
      (node (ref "J1") (pin "95") (pinfunction "H2-43_95") (pintype "passive+no_connect"))
    )
    (net (code "137") (name "unconnected-(J1-H2-44-Pad96)") (class "Default")
      (node (ref "J1") (pin "96") (pinfunction "H2-44_96") (pintype "passive+no_connect"))
    )
    (net (code "138") (name "unconnected-(J1-H2-45-Pad97)") (class "Default")
      (node (ref "J1") (pin "97") (pinfunction "H2-45_97") (pintype "passive+no_connect"))
    )
    (net (code "139") (name "unconnected-(J1-H2-46-Pad98)") (class "Default")
      (node (ref "J1") (pin "98") (pinfunction "H2-46_98") (pintype "passive+no_connect"))
    )
    (net (code "140") (name "unconnected-(J1-H2-47-Pad99)") (class "Default")
      (node (ref "J1") (pin "99") (pinfunction "H2-47_99") (pintype "passive+no_connect"))
    )
    (net (code "141") (name "unconnected-(J1-H2-48-Pad100)") (class "Default")
      (node (ref "J1") (pin "100") (pinfunction "H2-48_100") (pintype "passive+no_connect"))
    )
    (net (code "142") (name "unconnected-(J1-H2-49-Pad101)") (class "Default")
      (node (ref "J1") (pin "101") (pinfunction "H2-49_101") (pintype "passive+no_connect"))
    )
    (net (code "143") (name "unconnected-(J1-H2-50-Pad102)") (class "Default")
      (node (ref "J1") (pin "102") (pinfunction "H2-50_102") (pintype "passive+no_connect"))
    )
    (net (code "144") (name "unconnected-(J1-H2-51-Pad103)") (class "Default")
      (node (ref "J1") (pin "103") (pinfunction "H2-51_103") (pintype "passive+no_connect"))
    )
    (net (code "145") (name "unconnected-(J1-H2-52-Pad104)") (class "Default")
      (node (ref "J1") (pin "104") (pinfunction "H2-52_104") (pintype "passive+no_connect"))
    )
    (net (code "146") (name "unconnected-(J1-H3-3-Pad55)") (class "Default")
      (node (ref "J1") (pin "55") (pinfunction "H3-3_55") (pintype "passive+no_connect"))
    )
    (net (code "147") (name "unconnected-(U1-Pad10)") (class "Default")
      (node (ref "U1") (pin "10") (pinfunction "10_10") (pintype "passive+no_connect"))
    )
    (net (code "148") (name "unconnected-(U1-Pad11)") (class "Default")
      (node (ref "U1") (pin "11") (pinfunction "11_11") (pintype "passive+no_connect"))
    )
    (net (code "149") (name "unconnected-(U1-Pad12)") (class "Default")
      (node (ref "U1") (pin "12") (pinfunction "12_12") (pintype "passive+no_connect"))
    )
    (net (code "150") (name "unconnected-(U1-Pad13)") (class "Default")
      (node (ref "U1") (pin "13") (pinfunction "13_13") (pintype "passive+no_connect"))
    )
    (net (code "151") (name "unconnected-(U1-Pad15)") (class "Default")
      (node (ref "U1") (pin "15") (pinfunction "15_15") (pintype "passive+no_connect"))
    )
    (net (code "152") (name "unconnected-(U1-Pad19)") (class "Default")
      (node (ref "U1") (pin "19") (pinfunction "19_19") (pintype "passive+no_connect"))
    )
    (net (code "153") (name "unconnected-(U1-Pad20)") (class "Default")
      (node (ref "U1") (pin "20") (pinfunction "20_20") (pintype "passive+no_connect"))
    )
    (net (code "154") (name "unconnected-(U1-Pad22)") (class "Default")
      (node (ref "U1") (pin "22") (pinfunction "22_22") (pintype "passive+no_connect"))
    )
    (net (code "155") (name "unconnected-(U2-Pad10)") (class "Default")
      (node (ref "U2") (pin "10") (pinfunction "10_10") (pintype "passive+no_connect"))
    )
    (net (code "156") (name "unconnected-(U2-Pad11)") (class "Default")
      (node (ref "U2") (pin "11") (pinfunction "11_11") (pintype "passive+no_connect"))
    )
    (net (code "157") (name "unconnected-(U2-Pad12)") (class "Default")
      (node (ref "U2") (pin "12") (pinfunction "12_12") (pintype "passive+no_connect"))
    )
    (net (code "158") (name "unconnected-(U2-Pad13)") (class "Default")
      (node (ref "U2") (pin "13") (pinfunction "13_13") (pintype "passive+no_connect"))
    )
    (net (code "159") (name "unconnected-(U2-Pad15)") (class "Default")
      (node (ref "U2") (pin "15") (pinfunction "15_15") (pintype "passive+no_connect"))
    )
    (net (code "160") (name "unconnected-(U2-Pad19)") (class "Default")
      (node (ref "U2") (pin "19") (pinfunction "19_19") (pintype "passive+no_connect"))
    )
    (net (code "161") (name "unconnected-(U2-Pad20)") (class "Default")
      (node (ref "U2") (pin "20") (pinfunction "20_20") (pintype "passive+no_connect"))
    )
    (net (code "162") (name "unconnected-(U2-Pad22)") (class "Default")
      (node (ref "U2") (pin "22") (pinfunction "22_22") (pintype "passive+no_connect"))
    )
    (net (code "163") (name "unconnected-(U3-Pad10)") (class "Default")
      (node (ref "U3") (pin "10") (pinfunction "10_10") (pintype "passive+no_connect"))
    )
    (net (code "164") (name "unconnected-(U3-Pad11)") (class "Default")
      (node (ref "U3") (pin "11") (pinfunction "11_11") (pintype "passive+no_connect"))
    )
    (net (code "165") (name "unconnected-(U3-Pad12)") (class "Default")
      (node (ref "U3") (pin "12") (pinfunction "12_12") (pintype "passive+no_connect"))
    )
    (net (code "166") (name "unconnected-(U3-Pad13)") (class "Default")
      (node (ref "U3") (pin "13") (pinfunction "13_13") (pintype "passive+no_connect"))
    )
    (net (code "167") (name "unconnected-(U3-Pad15)") (class "Default")
      (node (ref "U3") (pin "15") (pinfunction "15_15") (pintype "passive+no_connect"))
    )
    (net (code "168") (name "unconnected-(U3-Pad19)") (class "Default")
      (node (ref "U3") (pin "19") (pinfunction "19_19") (pintype "passive+no_connect"))
    )
    (net (code "169") (name "unconnected-(U3-Pad20)") (class "Default")
      (node (ref "U3") (pin "20") (pinfunction "20_20") (pintype "passive+no_connect"))
    )
    (net (code "170") (name "unconnected-(U3-Pad22)") (class "Default")
      (node (ref "U3") (pin "22") (pinfunction "22_22") (pintype "passive+no_connect"))
    )
    (net (code "171") (name "unconnected-(U4-Pad10)") (class "Default")
      (node (ref "U4") (pin "10") (pinfunction "10_10") (pintype "passive+no_connect"))
    )
    (net (code "172") (name "unconnected-(U4-Pad11)") (class "Default")
      (node (ref "U4") (pin "11") (pinfunction "11_11") (pintype "passive+no_connect"))
    )
    (net (code "173") (name "unconnected-(U4-Pad12)") (class "Default")
      (node (ref "U4") (pin "12") (pinfunction "12_12") (pintype "passive+no_connect"))
    )
    (net (code "174") (name "unconnected-(U4-Pad13)") (class "Default")
      (node (ref "U4") (pin "13") (pinfunction "13_13") (pintype "passive+no_connect"))
    )
    (net (code "175") (name "unconnected-(U4-Pad15)") (class "Default")
      (node (ref "U4") (pin "15") (pinfunction "15_15") (pintype "passive+no_connect"))
    )
    (net (code "176") (name "unconnected-(U4-Pad19)") (class "Default")
      (node (ref "U4") (pin "19") (pinfunction "19_19") (pintype "passive+no_connect"))
    )
    (net (code "177") (name "unconnected-(U4-Pad20)") (class "Default")
      (node (ref "U4") (pin "20") (pinfunction "20_20") (pintype "passive+no_connect"))
    )
    (net (code "178") (name "unconnected-(U4-Pad22)") (class "Default")
      (node (ref "U4") (pin "22") (pinfunction "22_22") (pintype "passive+no_connect"))
    )
  )
)
